# Power.net
KiCad netlist of a schematic drawn in Altium Designer
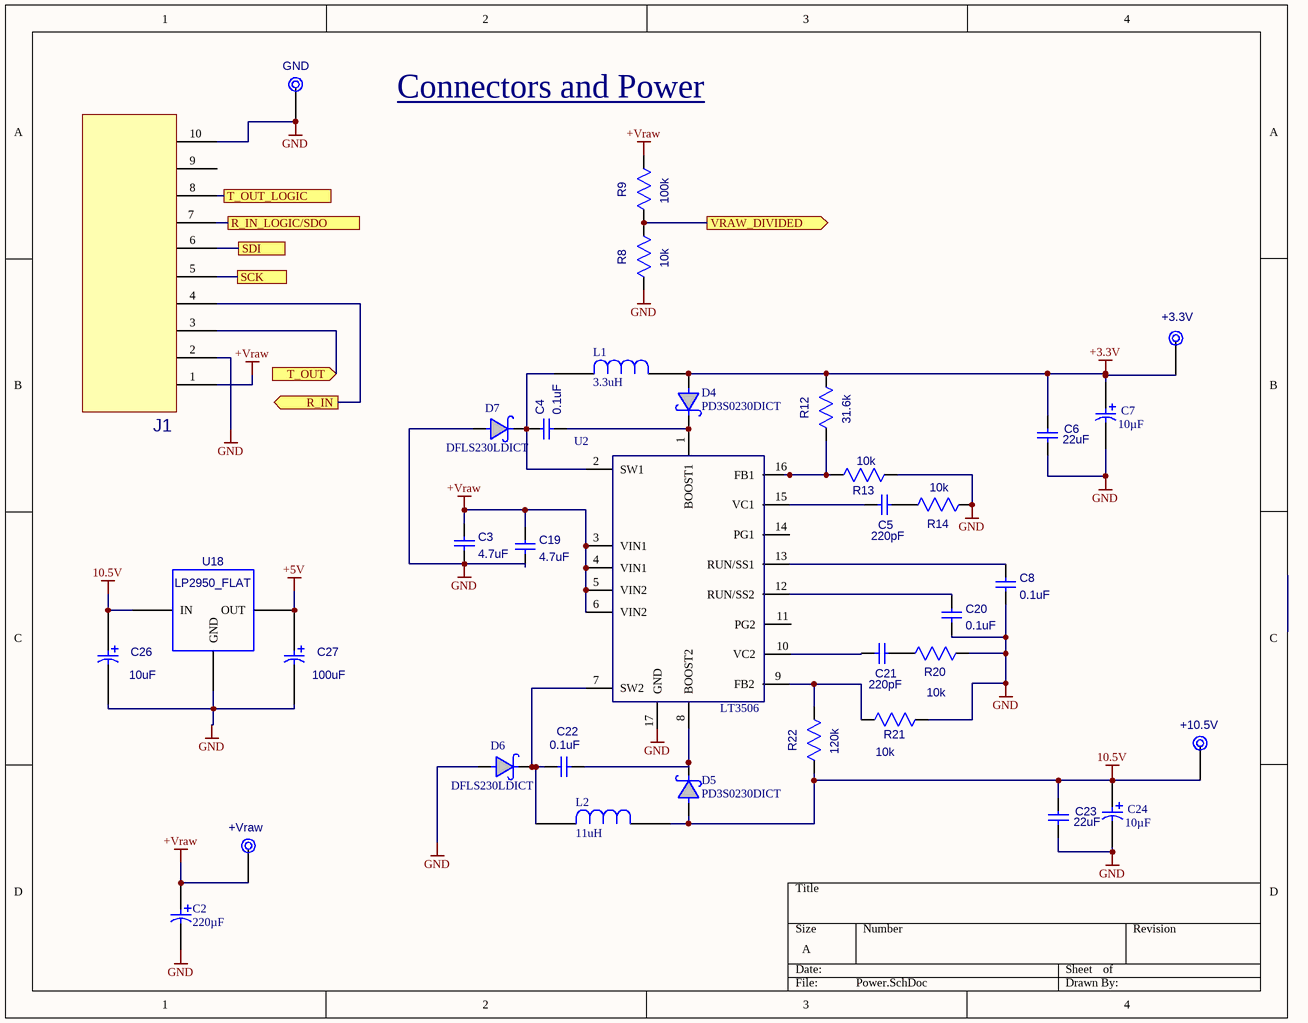
[diagram p0: Power.SchDoc]

(export (version "E")
  (design (tool "Eeschema 10.0.6"))
  (components
    (comp (ref "+5V")
      (value "+3.3V")
      (footprint "PAD_TESTPOINT")
      (description "Test Point")
      (libsource (lib "DBNOxVerI") (part "PAD"))
    )
    (comp (ref "+10.5V")
      (value "+10.5V")
      (footprint "PAD_TESTPOINT")
      (description "Test Point")
      (libsource (lib "DBNOxVerI") (part "PAD"))
    )
    (comp (ref "+Vraw")
      (value "+Vraw")
      (footprint "PAD_TESTPOINT")
      (description "Test Point")
      (libsource (lib "DBNOxVerI") (part "PAD"))
    )
    (comp (ref "C2")
      (value "CAP_POL_Alu")
      (footprint "Cap_Alu_UCL1V221MCL6GS")
      (fields
        (field (name "MANUFACTURER") "Nichicon")
        (field (name "TOLERANCE") "±20%")
        (field (name "MANUFACTURER PART NUMBER") "UCL1V221MCL6GS")
        (field (name "CAPACITANCE") "220µF")
      )
      (libsource (lib "DBNOxVerI") (part "CAP_POL_Alu"))
    )
    (comp (ref "C3")
      (value "4.7uF")
      (footprint "CC1206")
      (description "CC1206")
      (libsource (lib "DBNOxVerI") (part "CC1206"))
    )
    (comp (ref "C4")
      (value "0.1uF")
      (footprint "CC1206")
      (description "CC1206")
      (libsource (lib "DBNOxVerI") (part "CC1206"))
    )
    (comp (ref "C5")
      (value "220pF")
      (footprint "CC1206")
      (description "CC1206")
      (libsource (lib "DBNOxVerI") (part "CC1206"))
    )
    (comp (ref "C6")
      (value "22uF")
      (footprint "CC1206")
      (description "CC1206")
      (libsource (lib "DBNOxVerI") (part "CC1206"))
    )
    (comp (ref "C7")
      (value "CAP_POL_0805 Generic")
      (footprint "Cap_Pol_0805")
      (fields
        (field (name "MANUFACTURER") "Rohm Semiconductor")
        (field (name "MANUFACTURER PART NUMBER") "TCTP1C106M8R")
        (field (name "CAPACITANCE") "10µF")
        (field (name "TOLERANCE") "±20%")
      )
      (libsource (lib "DBNOxVerI") (part "CAP_POL_0805 Generic"))
    )
    (comp (ref "C8")
      (value "0.1uF")
      (footprint "CC1206")
      (description "CC1206")
      (libsource (lib "DBNOxVerI") (part "CC1206"))
    )
    (comp (ref "C19")
      (value "4.7uF")
      (footprint "CC1206")
      (description "CC1206")
      (libsource (lib "DBNOxVerI") (part "CC1206"))
    )
    (comp (ref "C20")
      (value "0.1uF")
      (footprint "CC1206")
      (description "CC1206")
      (libsource (lib "DBNOxVerI") (part "CC1206"))
    )
    (comp (ref "C21")
      (value "220pF")
      (footprint "CC1206")
      (description "CC1206")
      (libsource (lib "DBNOxVerI") (part "CC1206"))
    )
    (comp (ref "C22")
      (value "0.1uF")
      (footprint "CC1206")
      (description "CC1206")
      (libsource (lib "DBNOxVerI") (part "CC1206"))
    )
    (comp (ref "C23")
      (value "22uF")
      (footprint "CC1206")
      (description "CC1206")
      (libsource (lib "DBNOxVerI") (part "CC1206"))
    )
    (comp (ref "C24")
      (value "CAP_POL_0805 Generic")
      (footprint "Cap_Pol_0805")
      (fields
        (field (name "MANUFACTURER") "Rohm Semiconductor")
        (field (name "MANUFACTURER PART NUMBER") "TCTP1C106M8R")
        (field (name "CAPACITANCE") "10µF")
        (field (name "TOLERANCE") "±20%")
      )
      (libsource (lib "DBNOxVerI") (part "CAP_POL_0805 Generic"))
    )
    (comp (ref "C26")
      (value "10uF")
      (footprint "O3108:CAP_D_SMT_CAP_POL_D_PKG(Primary)")
      (description "CAP_POL_D_PKG")
      (libsource (lib "AQFlow_PCB") (part "CAP_POL_D_PKG"))
    )
    (comp (ref "C27")
      (value "100uF")
      (footprint "O3108:CAP_D_SMT_CAP_POL_D_PKG(Primary)")
      (description "CAP_POL_D_PKG")
      (libsource (lib "AQFlow_PCB") (part "CAP_POL_D_PKG"))
    )
    (comp (ref "D4")
      (value "PD3S0230DICT")
      (footprint "POWERDI123")
      (fields
        (field (name "MANUFACTURER") "Diodes Incorporated")
        (field (name "MANUFACTURER PART NUMBER") "PD3S0230-7")
      )
      (libsource (lib "DBNOxVerI") (part "PD3S0230DICT"))
    )
    (comp (ref "D5")
      (value "PD3S0230DICT")
      (footprint "POWERDI123")
      (fields
        (field (name "MANUFACTURER") "Diodes Incorporated")
        (field (name "MANUFACTURER PART NUMBER") "PD3S0230-7")
      )
      (libsource (lib "") (part "PD3S0230DICT_1"))
    )
    (comp (ref "D6")
      (value "DFLS230LDICT")
      (footprint "POWERDI123")
      (fields
        (field (name "MANUFACTURER") "Diodes Incorporated")
        (field (name "MANUFACTURER PART NUMBER") "DFLS230L-7")
      )
      (libsource (lib "DBNOxVerI") (part "DFLS230LDICT"))
    )
    (comp (ref "D7")
      (value "DFLS230LDICT")
      (footprint "POWERDI123")
      (fields
        (field (name "MANUFACTURER") "Diodes Incorporated")
        (field (name "MANUFACTURER PART NUMBER") "DFLS230L-7")
      )
      (libsource (lib "DBNOxVerI") (part "DFLS230LDICT"))
    )
    (comp (ref "GND")
      (value "GND")
      (footprint "PAD_TESTPOINT")
      (description "Test Point")
      (libsource (lib "DBNOxVerI") (part "PAD"))
    )
    (comp (ref "J1")
      (value "TERM_BLOCK_10")
      (footprint "Terminal Block 10 Pos")
      (libsource (lib "AQFlow_PCB") (part "TERM_BLOCK_10"))
    )
    (comp (ref "L1")
      (value "3.3uH")
      (footprint "Inductor_Small")
      (fields
        (field (name "MANUFACTURER") "Eaton Bussmann")
        (field (name "MANUFACTURER PART NUMBER") "EATON SD53-3R3-R")
        (field (name "TOLERANCE") "±20%")
      )
      (libsource (lib "DBNOxVerI") (part "Inductor"))
    )
    (comp (ref "L2")
      (value "11uH")
      (footprint "7447798111")
      (fields
        (field (name "MANUFACTURER") "Wurth Electronics Inc")
        (field (name "MANUFACTURER PART NUMBER") "7447798111")
        (field (name "TOLERANCE") "±20%")
      )
      (libsource (lib "AQFlow_PCB") (part "Inductor"))
    )
    (comp (ref "R8")
      (value "10k")
      (footprint "RC1206")
      (description "RC1206")
      (libsource (lib "AQFlow_PCB") (part "RC1206"))
    )
    (comp (ref "R9")
      (value "100k")
      (footprint "RC1206")
      (description "RC1206")
      (libsource (lib "DBNOxVerI") (part "RC1206"))
    )
    (comp (ref "R12")
      (value "31.6k")
      (footprint "RC1206")
      (description "RC1206")
      (libsource (lib "DBNOxVerI") (part "RC1206"))
    )
    (comp (ref "R13")
      (value "10k")
      (footprint "RC1206")
      (description "RC1206")
      (libsource (lib "DBNOxVerI") (part "RC1206"))
    )
    (comp (ref "R14")
      (value "10k")
      (footprint "RC1206")
      (description "RC1206")
      (libsource (lib "DBNOxVerI") (part "RC1206"))
    )
    (comp (ref "R20")
      (value "10k")
      (footprint "RC1206")
      (description "RC1206")
      (libsource (lib "DBNOxVerI") (part "RC1206"))
    )
    (comp (ref "R21")
      (value "10k")
      (footprint "RC1206")
      (description "RC1206")
      (libsource (lib "DBNOxVerI") (part "RC1206"))
    )
    (comp (ref "R22")
      (value "120k")
      (footprint "RC1206")
      (description "RC1206")
      (libsource (lib "DBNOxVerI") (part "RC1206"))
    )
    (comp (ref "U2")
      (value "LT3506")
      (footprint "TSSOP16 Bottom Pad")
      (fields
        (field (name "MANUFACTURER") "Linear Technology")
        (field (name "MANUFACTURER PART NUMBER") "LT3506AEFE#PBF")
      )
      (libsource (lib "DBNOxVerI") (part "LT3506"))
    )
    (comp (ref "U18")
      (value "LP2950_FLAT")
      (footprint "TO-252")
      (libsource (lib "AQFlow_PCB") (part "LP2950_FLAT"))
    )
  )
  (nets
    (net (code "1") (name "+3.3V") (class "Default")
      (node (ref "+5V") (pin "TP") (pintype "passive"))
      (node (ref "C6") (pin "1") (pintype "passive"))
      (node (ref "C7") (pin "plus") (pinfunction "plus_plus") (pintype "passive"))
      (node (ref "D4") (pin "A") (pinfunction "A_A") (pintype "passive"))
      (node (ref "L1") (pin "1") (pinfunction "1_1") (pintype "passive"))
      (node (ref "R12") (pin "1") (pinfunction "1_1") (pintype "passive"))
    )
    (net (code "2") (name "+5V") (class "Default")
      (node (ref "C27") (pin "plus") (pinfunction "plus_plus") (pintype "passive"))
      (node (ref "U18") (pin "3") (pinfunction "OUT_3") (pintype "passive"))
    )
    (net (code "3") (name "+Vraw") (class "Default")
      (node (ref "+Vraw") (pin "TP") (pintype "passive"))
      (node (ref "C19") (pin "1") (pintype "passive"))
      (node (ref "C2") (pin "plus") (pinfunction "plus_plus") (pintype "passive"))
      (node (ref "C3") (pin "1") (pintype "passive"))
      (node (ref "J1") (pin "1") (pinfunction "P1_1") (pintype "passive"))
      (node (ref "R9") (pin "1") (pinfunction "1_1") (pintype "passive"))
      (node (ref "U2") (pin "3") (pinfunction "VIN1_3") (pintype "passive"))
      (node (ref "U2") (pin "4") (pinfunction "VIN1_4") (pintype "passive"))
      (node (ref "U2") (pin "5") (pinfunction "VIN2_5") (pintype "passive"))
      (node (ref "U2") (pin "6") (pinfunction "VIN2_6") (pintype "passive"))
    )
    (net (code "4") (name "/R_IN") (class "Default")
      (node (ref "J1") (pin "4") (pinfunction "P4_4") (pintype "passive"))
    )
    (net (code "5") (name "/R_IN_LOGIC{slash}SDO") (class "Default")
      (node (ref "J1") (pin "7") (pinfunction "P7_7") (pintype "passive"))
    )
    (net (code "6") (name "/SCK") (class "Default")
      (node (ref "J1") (pin "5") (pinfunction "P5_5") (pintype "passive"))
    )
    (net (code "7") (name "/SDI") (class "Default")
      (node (ref "J1") (pin "6") (pinfunction "P6_6") (pintype "passive"))
    )
    (net (code "8") (name "/T_OUT") (class "Default")
      (node (ref "J1") (pin "3") (pinfunction "P3_3") (pintype "passive"))
    )
    (net (code "9") (name "/T_OUT_LOGIC") (class "Default")
      (node (ref "J1") (pin "8") (pinfunction "P8_8") (pintype "passive"))
    )
    (net (code "10") (name "/VRAW_DIVIDED") (class "Default")
      (node (ref "R8") (pin "1") (pinfunction "1_1") (pintype "passive"))
      (node (ref "R9") (pin "2") (pinfunction "2_2") (pintype "passive"))
    )
    (net (code "11") (name "10.5V") (class "Default")
      (node (ref "C26") (pin "plus") (pinfunction "plus_plus") (pintype "passive"))
      (node (ref "U18") (pin "1") (pinfunction "IN_1") (pintype "passive"))
    )
    (net (code "12") (name "GND") (class "Default")
      (node (ref "C19") (pin "2") (pintype "passive"))
      (node (ref "C2") (pin "minus") (pinfunction "minus_minus") (pintype "passive"))
      (node (ref "C20") (pin "2") (pintype "passive"))
      (node (ref "C23") (pin "2") (pintype "passive"))
      (node (ref "C24") (pin "minus") (pinfunction "minus_minus") (pintype "passive"))
      (node (ref "C26") (pin "minus") (pinfunction "minus_minus") (pintype "passive"))
      (node (ref "C27") (pin "minus") (pinfunction "minus_minus") (pintype "passive"))
      (node (ref "C3") (pin "2") (pintype "passive"))
      (node (ref "C6") (pin "2") (pintype "passive"))
      (node (ref "C7") (pin "minus") (pinfunction "minus_minus") (pintype "passive"))
      (node (ref "C8") (pin "2") (pintype "passive"))
      (node (ref "D6") (pin "A") (pinfunction "A_A") (pintype "passive"))
      (node (ref "D7") (pin "A") (pinfunction "A_A") (pintype "passive"))
      (node (ref "GND") (pin "TP") (pintype "passive"))
      (node (ref "J1") (pin "10") (pinfunction "P10_10") (pintype "passive"))
      (node (ref "J1") (pin "2") (pinfunction "P2_2") (pintype "passive"))
      (node (ref "R13") (pin "2") (pinfunction "2_2") (pintype "passive"))
      (node (ref "R14") (pin "2") (pinfunction "2_2") (pintype "passive"))
      (node (ref "R20") (pin "2") (pinfunction "2_2") (pintype "passive"))
      (node (ref "R21") (pin "2") (pinfunction "2_2") (pintype "passive"))
      (node (ref "R8") (pin "2") (pinfunction "2_2") (pintype "passive"))
      (node (ref "U18") (pin "2") (pinfunction "GND_2") (pintype "passive"))
      (node (ref "U2") (pin "17") (pinfunction "GND_17") (pintype "passive"))
    )
    (net (code "13") (name "Net-(+10.5V-PadTP)") (class "Default")
      (node (ref "+10.5V") (pin "TP") (pintype "passive"))
      (node (ref "C23") (pin "1") (pintype "passive"))
      (node (ref "C24") (pin "plus") (pinfunction "plus_plus") (pintype "passive"))
      (node (ref "D5") (pin "A") (pinfunction "A_A") (pintype "passive"))
      (node (ref "L2") (pin "1") (pinfunction "1_1") (pintype "passive"))
      (node (ref "R22") (pin "2") (pinfunction "2_2") (pintype "passive"))
    )
    (net (code "14") (name "Net-(C5-Pad1)") (class "Default")
      (node (ref "C5") (pin "1") (pintype "passive"))
      (node (ref "R14") (pin "1") (pinfunction "1_1") (pintype "passive"))
    )
    (net (code "15") (name "Net-(C21-Pad1)") (class "Default")
      (node (ref "C21") (pin "1") (pintype "passive"))
      (node (ref "R20") (pin "1") (pinfunction "1_1") (pintype "passive"))
    )
    (net (code "16") (name "Net-(U2-BOOST1)") (class "Default")
      (node (ref "C4") (pin "2") (pintype "passive"))
      (node (ref "D4") (pin "K") (pinfunction "K_K") (pintype "passive"))
      (node (ref "U2") (pin "1") (pinfunction "BOOST1_1") (pintype "passive"))
    )
    (net (code "17") (name "Net-(U2-BOOST2)") (class "Default")
      (node (ref "C22") (pin "2") (pintype "passive"))
      (node (ref "D5") (pin "K") (pinfunction "K_K") (pintype "passive"))
      (node (ref "U2") (pin "8") (pinfunction "BOOST2_8") (pintype "passive"))
    )
    (net (code "18") (name "Net-(U2-FB1)") (class "Default")
      (node (ref "R12") (pin "2") (pinfunction "2_2") (pintype "passive"))
      (node (ref "R13") (pin "1") (pinfunction "1_1") (pintype "passive"))
      (node (ref "U2") (pin "16") (pinfunction "FB1_16") (pintype "passive"))
    )
    (net (code "19") (name "Net-(U2-FB2)") (class "Default")
      (node (ref "R21") (pin "1") (pinfunction "1_1") (pintype "passive"))
      (node (ref "R22") (pin "1") (pinfunction "1_1") (pintype "passive"))
      (node (ref "U2") (pin "9") (pinfunction "FB2_9") (pintype "passive"))
    )
    (net (code "20") (name "Net-(U2-RUN{slash}SS1)") (class "Default")
      (node (ref "C8") (pin "1") (pintype "passive"))
      (node (ref "U2") (pin "13") (pinfunction "RUN/SS1_13") (pintype "passive"))
    )
    (net (code "21") (name "Net-(U2-RUN{slash}SS2)") (class "Default")
      (node (ref "C20") (pin "1") (pintype "passive"))
      (node (ref "U2") (pin "12") (pinfunction "RUN/SS2_12") (pintype "passive"))
    )
    (net (code "22") (name "Net-(U2-SW1)") (class "Default")
      (node (ref "C4") (pin "1") (pintype "passive"))
      (node (ref "D7") (pin "K") (pinfunction "K_K") (pintype "passive"))
      (node (ref "L1") (pin "2") (pinfunction "2_2") (pintype "passive"))
      (node (ref "U2") (pin "2") (pinfunction "SW1_2") (pintype "passive"))
    )
    (net (code "23") (name "Net-(U2-SW2)") (class "Default")
      (node (ref "C22") (pin "1") (pintype "passive"))
      (node (ref "D6") (pin "K") (pinfunction "K_K") (pintype "passive"))
      (node (ref "L2") (pin "2") (pinfunction "2_2") (pintype "passive"))
      (node (ref "U2") (pin "7") (pinfunction "SW2_7") (pintype "passive"))
    )
    (net (code "24") (name "Net-(U2-VC1)") (class "Default")
      (node (ref "C5") (pin "2") (pintype "passive"))
      (node (ref "U2") (pin "15") (pinfunction "VC1_15") (pintype "passive"))
    )
    (net (code "25") (name "Net-(U2-VC2)") (class "Default")
      (node (ref "C21") (pin "2") (pintype "passive"))
      (node (ref "U2") (pin "10") (pinfunction "VC2_10") (pintype "passive"))
    )
    (net (code "26") (name "unconnected-(J1-P9-Pad9)") (class "Default")
      (node (ref "J1") (pin "9") (pinfunction "P9_9") (pintype "passive"))
    )
    (net (code "27") (name "unconnected-(U2-PG1-Pad14)") (class "Default")
      (node (ref "U2") (pin "14") (pinfunction "PG1_14") (pintype "passive"))
    )
    (net (code "28") (name "unconnected-(U2-PG2-Pad11)") (class "Default")
      (node (ref "U2") (pin "11") (pinfunction "PG2_11") (pintype "passive"))
    )
  )
)
